# Main.net
KiCad netlist of a schematic drawn in Altium Designer
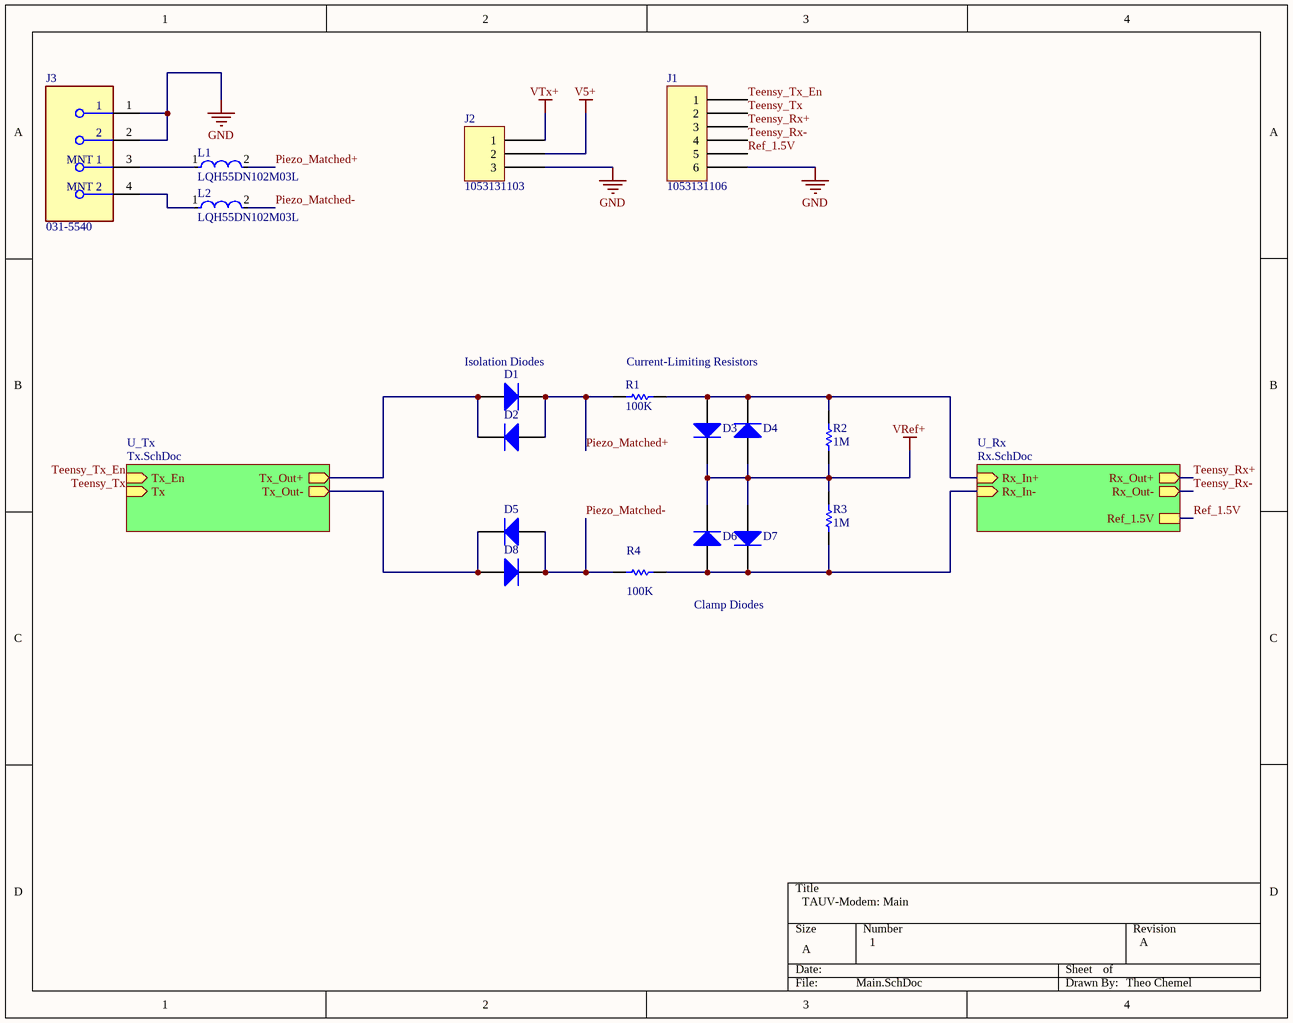
[diagram p0: Main.SchDoc]

(export (version "E")
  (design (tool "Eeschema 10.0.6"))
  (components
    (comp (ref "D1")
      (value "Diode")
      (footprint "SOD-123F")
      (libsource (lib "Simulation Generic Components") (part "Diode"))
    )
    (comp (ref "D2")
      (value "Diode")
      (footprint "SOD-123F")
      (libsource (lib "Simulation Generic Components") (part "Diode"))
    )
    (comp (ref "D3")
      (value "Diode")
      (footprint "SOD-123F")
      (libsource (lib "Simulation Generic Components") (part "Diode"))
    )
    (comp (ref "D4")
      (value "Diode")
      (footprint "SOD-123F")
      (libsource (lib "Simulation Generic Components") (part "Diode"))
    )
    (comp (ref "D5")
      (value "Diode")
      (footprint "SOD-123F")
      (libsource (lib "Simulation Generic Components") (part "Diode"))
    )
    (comp (ref "D6")
      (value "Diode")
      (footprint "SOD-123F")
      (libsource (lib "Simulation Generic Components") (part "Diode"))
    )
    (comp (ref "D7")
      (value "Diode")
      (footprint "SOD-123F")
      (libsource (lib "Simulation Generic Components") (part "Diode"))
    )
    (comp (ref "D8")
      (value "Diode")
      (footprint "SOD-123F")
      (libsource (lib "Simulation Generic Components") (part "Diode"))
    )
    (comp (ref "J1")
      (value "1053131106")
      (footprint "MOLEX 1053131106")
      (description "CONN HEADER R/A 6POS 2.5MM")
      (fields (field (name "MANUFACTURER") "Molex"))
      (libsource (lib "Celestial Altium Library - altium_library") (part "6 Pin"))
    )
    (comp (ref "J2")
      (value "1053131103")
      (footprint "MOLEX 1053131103")
      (description "CONN HEADER R/A 3POS 2.5MM")
      (fields (field (name "MANUFACTURER") "Molex"))
      (libsource (lib "Celestial Altium Library - altium_library") (part "3 Pin"))
    )
    (comp (ref "J3")
      (value "031-5540")
      (footprint "FP-031-5540-MFG")
      (description "CONN BNC RCPT R/A 50 OHM PCB")
      (fields
        (field (name "OCTOPART") "https://octopart.com/031-5540-amphenol+rf-49742301")
        (field (name "MANUFACTURER") "Amphenol RF")
      )
      (libsource (lib "Altium Content Vault") (part "c4223d6e67c9a5a609df11ee682ef75"))
    )
    (comp (ref "L1")
      (value "LQH55DN102M03L")
      (footprint "FP-LQH55DN_03-MFG")
      (description "Wire Wound Ferrite Inductor for Power Lines 1000μH ±20% 14.42Ω  0.15A 2220")
      (fields (field (name "TOLERANCE") "20%"))
      (libsource (lib "Altium Content Vault") (part "725321dda6339637d4d059423bc1c3c"))
    )
    (comp (ref "L2")
      (value "LQH55DN102M03L")
      (footprint "FP-LQH55DN_03-MFG")
      (description "Wire Wound Ferrite Inductor for Power Lines 1000μH ±20% 14.42Ω  0.15A 2220")
      (fields (field (name "TOLERANCE") "20%"))
      (libsource (lib "Altium Content Vault") (part "725321dda6339637d4d059423bc1c3c"))
    )
    (comp (ref "R1")
      (value "100K")
      (footprint "0805")
      (description "Resistor")
      (libsource (lib "Simulation Generic Components") (part "Resistor"))
    )
    (comp (ref "R2")
      (value "1M")
      (footprint "0805")
      (description "Resistor")
      (libsource (lib "Simulation Generic Components") (part "Resistor"))
    )
    (comp (ref "R3")
      (value "1M")
      (footprint "0805")
      (description "Resistor")
      (libsource (lib "Simulation Generic Components") (part "Resistor"))
    )
    (comp (ref "R4")
      (value "100K")
      (footprint "0805")
      (description "Resistor")
      (libsource (lib "Simulation Generic Components") (part "Resistor"))
    )
  )
  (nets
    (net (code "1") (name "/Piezo_Matched+") (class "Default")
      (node (ref "D1") (pin "2") (pinfunction "K_2") (pintype "passive"))
      (node (ref "D2") (pin "1") (pinfunction "A_1") (pintype "passive"))
      (node (ref "L1") (pin "2") (pinfunction "2_2") (pintype "passive"))
      (node (ref "R1") (pin "1") (pinfunction "1_1") (pintype "passive"))
    )
    (net (code "2") (name "/Piezo_Matched-") (class "Default")
      (node (ref "D5") (pin "1") (pinfunction "A_1") (pintype "passive"))
      (node (ref "D8") (pin "2") (pinfunction "K_2") (pintype "passive"))
      (node (ref "L2") (pin "2") (pinfunction "2_2") (pintype "passive"))
      (node (ref "R4") (pin "1") (pinfunction "1_1") (pintype "passive"))
    )
    (net (code "3") (name "/Ref_1.5V") (class "Default")
      (node (ref "J1") (pin "5") (pinfunction "5_5") (pintype "passive"))
    )
    (net (code "4") (name "/Rx_In+") (class "Default")
      (node (ref "D3") (pin "1") (pinfunction "A_1") (pintype "passive"))
      (node (ref "D4") (pin "2") (pinfunction "K_2") (pintype "passive"))
      (node (ref "R1") (pin "2") (pinfunction "2_2") (pintype "passive"))
      (node (ref "R2") (pin "2") (pinfunction "2_2") (pintype "passive"))
    )
    (net (code "5") (name "/Rx_In-") (class "Default")
      (node (ref "D6") (pin "1") (pinfunction "A_1") (pintype "passive"))
      (node (ref "D7") (pin "2") (pinfunction "K_2") (pintype "passive"))
      (node (ref "R3") (pin "1") (pinfunction "1_1") (pintype "passive"))
      (node (ref "R4") (pin "2") (pinfunction "2_2") (pintype "passive"))
    )
    (net (code "6") (name "/Teensy_Rx+") (class "Default")
      (node (ref "J1") (pin "3") (pinfunction "3_3") (pintype "passive"))
    )
    (net (code "7") (name "/Teensy_Rx-") (class "Default")
      (node (ref "J1") (pin "4") (pinfunction "4_4") (pintype "passive"))
    )
    (net (code "8") (name "/Teensy_Tx") (class "Default")
      (node (ref "J1") (pin "2") (pinfunction "2_2") (pintype "passive"))
    )
    (net (code "9") (name "/Teensy_Tx_En") (class "Default")
      (node (ref "J1") (pin "1") (pinfunction "1_1") (pintype "passive"))
    )
    (net (code "10") (name "/Tx_Out+") (class "Default")
      (node (ref "D1") (pin "1") (pinfunction "A_1") (pintype "passive"))
      (node (ref "D2") (pin "2") (pinfunction "K_2") (pintype "passive"))
    )
    (net (code "11") (name "/Tx_Out-") (class "Default")
      (node (ref "D5") (pin "2") (pinfunction "K_2") (pintype "passive"))
      (node (ref "D8") (pin "1") (pinfunction "A_1") (pintype "passive"))
    )
    (net (code "12") (name "GND") (class "Default")
      (node (ref "J1") (pin "6") (pinfunction "6_6") (pintype "passive"))
      (node (ref "J2") (pin "3") (pinfunction "3_3") (pintype "passive"))
      (node (ref "J3") (pin "1") (pinfunction "1_1") (pintype "passive"))
      (node (ref "J3") (pin "2") (pinfunction "2_2") (pintype "passive"))
    )
    (net (code "13") (name "Net-(J3-MNT_1)") (class "Default")
      (node (ref "J3") (pin "3") (pinfunction "MNT_1_3") (pintype "passive"))
      (node (ref "L1") (pin "1") (pinfunction "1_1") (pintype "passive"))
    )
    (net (code "14") (name "Net-(J3-MNT_2)") (class "Default")
      (node (ref "J3") (pin "4") (pinfunction "MNT_2_4") (pintype "passive"))
      (node (ref "L2") (pin "1") (pinfunction "1_1") (pintype "passive"))
    )
    (net (code "15") (name "V5+") (class "Default")
      (node (ref "J2") (pin "2") (pinfunction "2_2") (pintype "passive"))
    )
    (net (code "16") (name "VRef+") (class "Default")
      (node (ref "D3") (pin "2") (pinfunction "K_2") (pintype "passive"))
      (node (ref "D4") (pin "1") (pinfunction "A_1") (pintype "passive"))
      (node (ref "D6") (pin "2") (pinfunction "K_2") (pintype "passive"))
      (node (ref "D7") (pin "1") (pinfunction "A_1") (pintype "passive"))
      (node (ref "R2") (pin "1") (pinfunction "1_1") (pintype "passive"))
      (node (ref "R3") (pin "2") (pinfunction "2_2") (pintype "passive"))
    )
    (net (code "17") (name "VTx+") (class "Default")
      (node (ref "J2") (pin "1") (pinfunction "1_1") (pintype "passive"))
    )
  )
)
